# brain.net
KiCad netlist of a schematic drawn in EAGLE
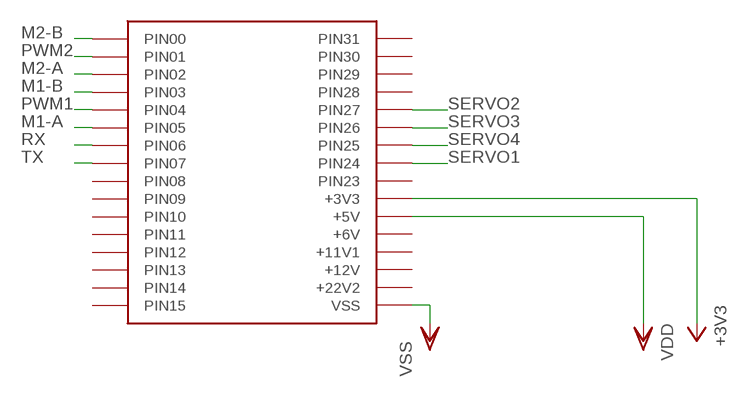
[diagram p0: schematic, sheet 1]
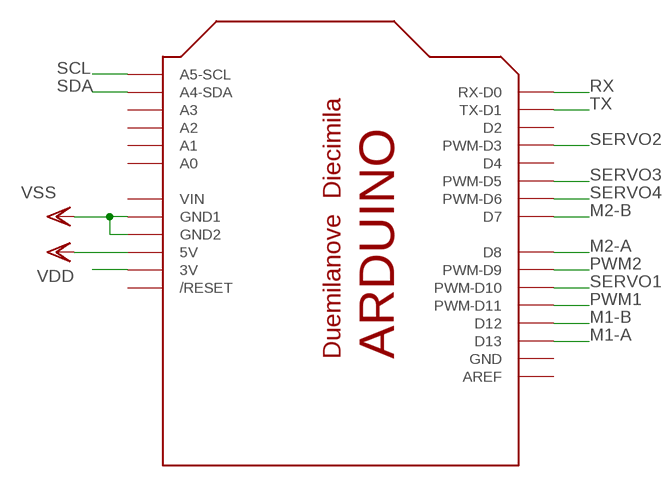
[diagram p1: schematic, sheet 2]
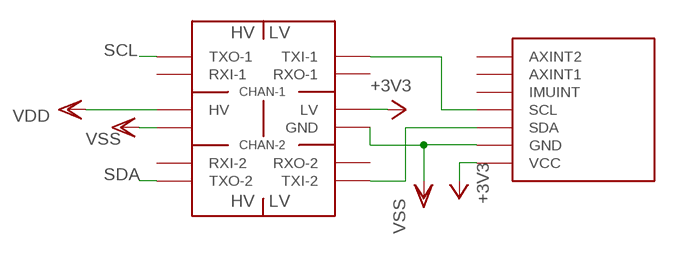
[diagram p2: schematic, sheet 3]

(export (version "E")
  (design (tool "Eeschema 10.0.6"))
  (components
    (comp (ref "U$6")
      (value "ARDUINOUNO")
      (footprint "eagle-import:ARDUINO")
      (libsource (lib "eagle-import") (part "ARDUINOUNO"))
    )
    (comp (ref "U$1")
      (value "BASE")
      (footprint "eagle-import:BASE")
      (libsource (lib "eagle-import") (part "BASE"))
    )
    (comp (ref "U$7")
      (value "IMU3000COMBO")
      (footprint "eagle-import:IMU3000-COMBO")
      (libsource (lib "eagle-import") (part "IMU3000COMBO"))
    )
    (comp (ref "U$8")
      (value "LOGIC-LEVEL-CONVERTER")
      (footprint "eagle-import:LEVEL-CONVERTER")
      (libsource (lib "eagle-import") (part "LOGIC-LEVEL-CONVERTER"))
    )
  )
  (nets
    (net (code "1") (name "+3V3") (class "Default")
      (node (ref "U$1") (pin "PIN22") (pinfunction "+3V3_PIN22") (pintype "bidirectional"))
      (node (ref "U$7") (pin "3V3") (pinfunction "VCC_3V3") (pintype "power_in"))
      (node (ref "U$8") (pin "P$3") (pinfunction "LV_P$3") (pintype "power_in"))
    )
    (net (code "2") (name "GND") (class "Default")
      (node (ref "U$6") (pin "GND") (pinfunction "GND_GND") (pintype "power_in"))
    )
    (net (code "3") (name "M1-A") (class "Default")
      (node (ref "U$1") (pin "PIN05") (pinfunction "PIN05_PIN05") (pintype "bidirectional"))
      (node (ref "U$6") (pin "D13") (pinfunction "D13_D13") (pintype "bidirectional"))
    )
    (net (code "4") (name "M1-B") (class "Default")
      (node (ref "U$1") (pin "PIN03") (pinfunction "PIN03_PIN03") (pintype "bidirectional"))
      (node (ref "U$6") (pin "D12") (pinfunction "D12_D12") (pintype "bidirectional"))
    )
    (net (code "5") (name "M2-A") (class "Default")
      (node (ref "U$1") (pin "PIN02") (pinfunction "PIN02_PIN02") (pintype "bidirectional"))
      (node (ref "U$6") (pin "D8") (pinfunction "D8_D8") (pintype "bidirectional"))
    )
    (net (code "6") (name "M2-B") (class "Default")
      (node (ref "U$1") (pin "PIN00") (pinfunction "PIN00_PIN00") (pintype "bidirectional"))
      (node (ref "U$6") (pin "D7") (pinfunction "D7_D7") (pintype "bidirectional"))
    )
    (net (code "7") (name "Net-(U$8-TXI-1)") (class "Default")
      (node (ref "U$7") (pin "SCL") (pinfunction "SCL_SCL") (pintype "bidirectional"))
      (node (ref "U$8") (pin "P$1") (pinfunction "TXI-1_P$1") (pintype "bidirectional"))
    )
    (net (code "8") (name "Net-(U$8-TXI-2)") (class "Default")
      (node (ref "U$7") (pin "SDA") (pinfunction "SDA_SDA") (pintype "bidirectional"))
      (node (ref "U$8") (pin "P$6") (pinfunction "TXI-2_P$6") (pintype "bidirectional"))
    )
    (net (code "9") (name "PWM1") (class "Default")
      (node (ref "U$1") (pin "PIN04") (pinfunction "PIN04_PIN04") (pintype "bidirectional"))
      (node (ref "U$6") (pin "D11") (pinfunction "PWM-D11_D11") (pintype "bidirectional"))
    )
    (net (code "10") (name "PWM2") (class "Default")
      (node (ref "U$1") (pin "PIN01") (pinfunction "PIN01_PIN01") (pintype "bidirectional"))
      (node (ref "U$6") (pin "D9") (pinfunction "PWM-D9_D9") (pintype "bidirectional"))
    )
    (net (code "11") (name "RX") (class "Default")
      (node (ref "U$1") (pin "PIN06") (pinfunction "PIN06_PIN06") (pintype "bidirectional"))
      (node (ref "U$6") (pin "D0") (pinfunction "RX-D0_D0") (pintype "bidirectional"))
    )
    (net (code "12") (name "SCL") (class "Default")
      (node (ref "U$6") (pin "A5") (pinfunction "A5-SCL_A5") (pintype "bidirectional"))
      (node (ref "U$8") (pin "P$12") (pinfunction "TXO-1_P$12") (pintype "bidirectional"))
    )
    (net (code "13") (name "SDA") (class "Default")
      (node (ref "U$6") (pin "A4") (pinfunction "A4-SDA_A4") (pintype "bidirectional"))
      (node (ref "U$8") (pin "P$7") (pinfunction "TXO-2_P$7") (pintype "bidirectional"))
    )
    (net (code "14") (name "SERVO1") (class "Default")
      (node (ref "U$1") (pin "PIN24") (pinfunction "PIN24_PIN24") (pintype "bidirectional"))
      (node (ref "U$6") (pin "D10") (pinfunction "PWM-D10_D10") (pintype "bidirectional"))
    )
    (net (code "15") (name "SERVO2") (class "Default")
      (node (ref "U$1") (pin "PIN27") (pinfunction "PIN27_PIN27") (pintype "bidirectional"))
      (node (ref "U$6") (pin "D3") (pinfunction "PWM-D3_D3") (pintype "bidirectional"))
    )
    (net (code "16") (name "SERVO3") (class "Default")
      (node (ref "U$1") (pin "PIN26") (pinfunction "PIN26_PIN26") (pintype "bidirectional"))
      (node (ref "U$6") (pin "D5") (pinfunction "PWM-D5_D5") (pintype "bidirectional"))
    )
    (net (code "17") (name "SERVO4") (class "Default")
      (node (ref "U$1") (pin "PIN25") (pinfunction "PIN25_PIN25") (pintype "bidirectional"))
      (node (ref "U$6") (pin "D6") (pinfunction "PWM-D6_D6") (pintype "bidirectional"))
    )
    (net (code "18") (name "TX") (class "Default")
      (node (ref "U$1") (pin "PIN07") (pinfunction "PIN07_PIN07") (pintype "bidirectional"))
      (node (ref "U$6") (pin "D1") (pinfunction "TX-D1_D1") (pintype "bidirectional"))
    )
    (net (code "19") (name "VDD") (class "Default")
      (node (ref "U$1") (pin "PIN21") (pinfunction "+5V_PIN21") (pintype "bidirectional"))
      (node (ref "U$6") (pin "5V") (pinfunction "5V_5V") (pintype "power_in"))
      (node (ref "U$8") (pin "P$10") (pinfunction "HV_P$10") (pintype "power_in"))
    )
    (net (code "20") (name "VIN") (class "Default")
      (node (ref "U$6") (pin "VIN") (pinfunction "VIN_VIN") (pintype "power_in"))
    )
    (net (code "21") (name "VSS") (class "Default")
      (node (ref "U$1") (pin "PIN16") (pinfunction "VSS_PIN16") (pintype "bidirectional"))
      (node (ref "U$6") (pin "GND1") (pinfunction "GND1_GND1") (pintype "power_in"))
      (node (ref "U$6") (pin "GND2") (pinfunction "GND2_GND2") (pintype "power_in"))
      (node (ref "U$7") (pin "VSS") (pinfunction "GND_VSS") (pintype "power_in"))
      (node (ref "U$8") (pin "P$4") (pinfunction "GND_P$4") (pintype "power_in"))
      (node (ref "U$8") (pin "P$9") (pintype "power_in"))
    )
    (net (code "22") (name "unconnected-(U$1-+6V-PadPIN20)") (class "Default")
      (node (ref "U$1") (pin "PIN20") (pinfunction "+6V_PIN20") (pintype "bidirectional"))
    )
    (net (code "23") (name "unconnected-(U$1-+11V1-PadPIN19)") (class "Default")
      (node (ref "U$1") (pin "PIN19") (pinfunction "+11V1_PIN19") (pintype "bidirectional"))
    )
    (net (code "24") (name "unconnected-(U$1-+12V-PadPIN18)") (class "Default")
      (node (ref "U$1") (pin "PIN18") (pinfunction "+12V_PIN18") (pintype "bidirectional"))
    )
    (net (code "25") (name "unconnected-(U$1-+22V2-PadPIN17)") (class "Default")
      (node (ref "U$1") (pin "PIN17") (pinfunction "+22V2_PIN17") (pintype "bidirectional"))
    )
    (net (code "26") (name "unconnected-(U$1-PadPIN08)") (class "Default")
      (node (ref "U$1") (pin "PIN08") (pinfunction "PIN08_PIN08") (pintype "bidirectional"))
    )
    (net (code "27") (name "unconnected-(U$1-PadPIN09)") (class "Default")
      (node (ref "U$1") (pin "PIN09") (pinfunction "PIN09_PIN09") (pintype "bidirectional"))
    )
    (net (code "28") (name "unconnected-(U$1-PadPIN10)") (class "Default")
      (node (ref "U$1") (pin "PIN10") (pinfunction "PIN10_PIN10") (pintype "bidirectional"))
    )
    (net (code "29") (name "unconnected-(U$1-PadPIN11)") (class "Default")
      (node (ref "U$1") (pin "PIN11") (pinfunction "PIN11_PIN11") (pintype "bidirectional"))
    )
    (net (code "30") (name "unconnected-(U$1-PadPIN12)") (class "Default")
      (node (ref "U$1") (pin "PIN12") (pinfunction "PIN12_PIN12") (pintype "bidirectional"))
    )
    (net (code "31") (name "unconnected-(U$1-PadPIN13)") (class "Default")
      (node (ref "U$1") (pin "PIN13") (pinfunction "PIN13_PIN13") (pintype "bidirectional"))
    )
    (net (code "32") (name "unconnected-(U$1-PadPIN14)") (class "Default")
      (node (ref "U$1") (pin "PIN14") (pinfunction "PIN14_PIN14") (pintype "bidirectional"))
    )
    (net (code "33") (name "unconnected-(U$1-PadPIN15)") (class "Default")
      (node (ref "U$1") (pin "PIN15") (pinfunction "PIN15_PIN15") (pintype "bidirectional"))
    )
    (net (code "34") (name "unconnected-(U$1-PadPIN23)") (class "Default")
      (node (ref "U$1") (pin "PIN23") (pinfunction "PIN23_PIN23") (pintype "bidirectional"))
    )
    (net (code "35") (name "unconnected-(U$1-PadPIN28)") (class "Default")
      (node (ref "U$1") (pin "PIN28") (pinfunction "PIN28_PIN28") (pintype "bidirectional"))
    )
    (net (code "36") (name "unconnected-(U$1-PadPIN29)") (class "Default")
      (node (ref "U$1") (pin "PIN29") (pinfunction "PIN29_PIN29") (pintype "bidirectional"))
    )
    (net (code "37") (name "unconnected-(U$1-PadPIN30)") (class "Default")
      (node (ref "U$1") (pin "PIN30") (pinfunction "PIN30_PIN30") (pintype "bidirectional"))
    )
    (net (code "38") (name "unconnected-(U$1-PadPIN31)") (class "Default")
      (node (ref "U$1") (pin "PIN31") (pinfunction "PIN31_PIN31") (pintype "bidirectional"))
    )
    (net (code "39") (name "unconnected-(U$6-Pad3V)") (class "Default")
      (node (ref "U$6") (pin "3V") (pinfunction "3V_3V") (pintype "power_in"))
    )
    (net (code "40") (name "unconnected-(U$6-PadA0)") (class "Default")
      (node (ref "U$6") (pin "A0") (pinfunction "A0_A0") (pintype "bidirectional"))
    )
    (net (code "41") (name "unconnected-(U$6-PadA1)") (class "Default")
      (node (ref "U$6") (pin "A1") (pinfunction "A1_A1") (pintype "bidirectional"))
    )
    (net (code "42") (name "unconnected-(U$6-PadA2)") (class "Default")
      (node (ref "U$6") (pin "A2") (pinfunction "A2_A2") (pintype "bidirectional"))
    )
    (net (code "43") (name "unconnected-(U$6-PadA3)") (class "Default")
      (node (ref "U$6") (pin "A3") (pinfunction "A3_A3") (pintype "bidirectional"))
    )
    (net (code "44") (name "unconnected-(U$6-PadAREF)") (class "Default")
      (node (ref "U$6") (pin "AREF") (pinfunction "AREF_AREF") (pintype "bidirectional"))
    )
    (net (code "45") (name "unconnected-(U$6-PadD2)") (class "Default")
      (node (ref "U$6") (pin "D2") (pinfunction "D2_D2") (pintype "bidirectional"))
    )
    (net (code "46") (name "unconnected-(U$6-PadD4)") (class "Default")
      (node (ref "U$6") (pin "D4") (pinfunction "D4_D4") (pintype "bidirectional"))
    )
    (net (code "47") (name "unconnected-(U$6-{slash}RESET-PadRESET)") (class "Default")
      (node (ref "U$6") (pin "RESET") (pinfunction "/RESET_RESET") (pintype "bidirectional"))
    )
    (net (code "48") (name "unconnected-(U$7-PadAXINT1)") (class "Default")
      (node (ref "U$7") (pin "AXINT1") (pinfunction "AXINT1_AXINT1") (pintype "bidirectional"))
    )
    (net (code "49") (name "unconnected-(U$7-PadAXINT2)") (class "Default")
      (node (ref "U$7") (pin "AXINT2") (pinfunction "AXINT2_AXINT2") (pintype "bidirectional"))
    )
    (net (code "50") (name "unconnected-(U$7-PadIMUINT)") (class "Default")
      (node (ref "U$7") (pin "IMUINT") (pinfunction "IMUINT_IMUINT") (pintype "bidirectional"))
    )
    (net (code "51") (name "unconnected-(U$8-RXI-1-PadP$11)") (class "Default")
      (node (ref "U$8") (pin "P$11") (pinfunction "RXI-1_P$11") (pintype "bidirectional"))
    )
    (net (code "52") (name "unconnected-(U$8-RXI-2-PadP$8)") (class "Default")
      (node (ref "U$8") (pin "P$8") (pinfunction "RXI-2_P$8") (pintype "bidirectional"))
    )
    (net (code "53") (name "unconnected-(U$8-RXO-1-PadP$2)") (class "Default")
      (node (ref "U$8") (pin "P$2") (pinfunction "RXO-1_P$2") (pintype "bidirectional"))
    )
    (net (code "54") (name "unconnected-(U$8-RXO-2-PadP$5)") (class "Default")
      (node (ref "U$8") (pin "P$5") (pinfunction "RXO-2_P$5") (pintype "bidirectional"))
    )
  )
)
